# Led_PCB_v2_0.net
KiCad netlist of a schematic drawn in EAGLE
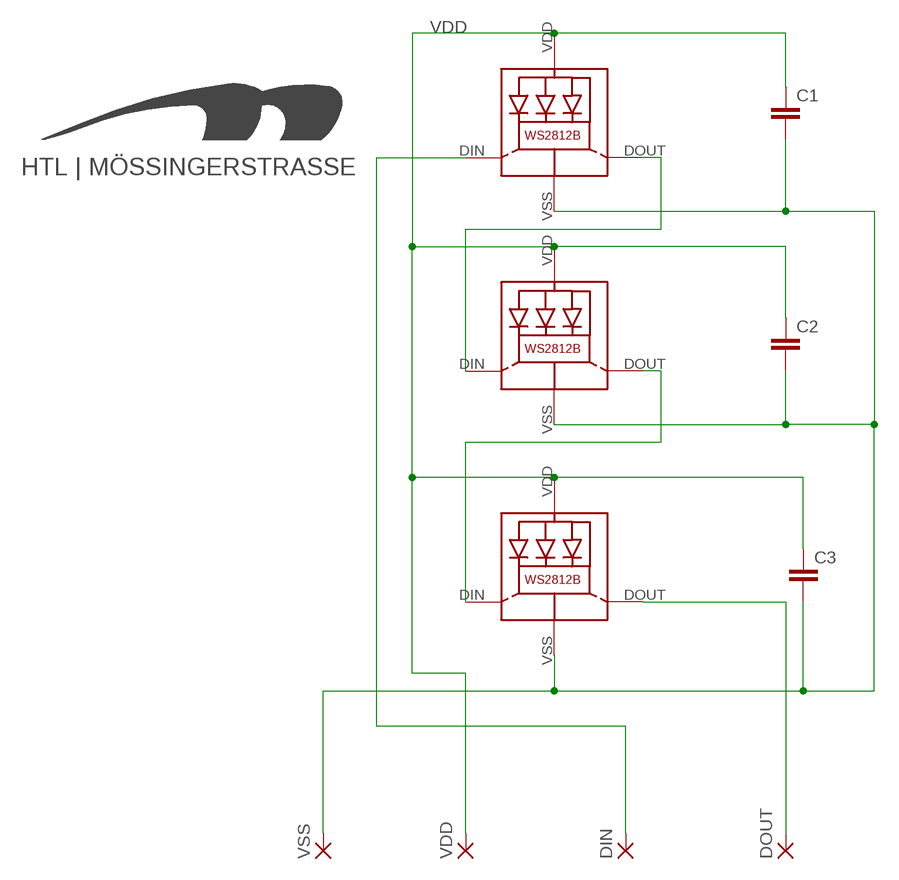
[diagram p0: schematic, sheet 1]

(export (version "E")
  (design (tool "Eeschema 10.0.6"))
  (components
    (comp (ref "C1")
      (value "C-EUC0805")
      (footprint "eagle-import:C0805")
      (libsource (lib "eagle-import") (part "C-EUC0805"))
    )
    (comp (ref "C2")
      (value "C-EUC0805")
      (footprint "eagle-import:C0805")
      (libsource (lib "eagle-import") (part "C-EUC0805"))
    )
    (comp (ref "C3")
      (value "C-EUC0805")
      (footprint "eagle-import:C0805")
      (libsource (lib "eagle-import") (part "C-EUC0805"))
    )
    (comp (ref "DIN")
      (value "SMD2")
      (footprint "eagle-import:SMD1,27-2,54")
      (libsource (lib "eagle-import") (part "SMD2"))
    )
    (comp (ref "DOUT")
      (value "SMD2")
      (footprint "eagle-import:SMD1,27-2,54")
      (libsource (lib "eagle-import") (part "SMD2"))
    )
    (comp (ref "LED1")
      (value "WS2812B")
      (footprint "eagle-import:WS2812B")
      (libsource (lib "eagle-import") (part "WS2812B"))
    )
    (comp (ref "LED2")
      (value "WS2812B")
      (footprint "eagle-import:WS2812B")
      (libsource (lib "eagle-import") (part "WS2812B"))
    )
    (comp (ref "LED3")
      (value "WS2812B")
      (footprint "eagle-import:WS2812B")
      (libsource (lib "eagle-import") (part "WS2812B"))
    )
    (comp (ref "U$1")
      (value "HTL_LOGOTOP_8MM")
      (footprint "eagle-import:LOGOTOP_8")
      (libsource (lib "eagle-import") (part "HTL_LOGOTOP_8MM"))
    )
    (comp (ref "VDD")
      (value "SMD2")
      (footprint "eagle-import:SMD1,27-2,54")
      (libsource (lib "eagle-import") (part "SMD2"))
    )
    (comp (ref "VSS")
      (value "SMD2")
      (footprint "eagle-import:SMD1,27-2,54")
      (libsource (lib "eagle-import") (part "SMD2"))
    )
  )
  (nets
    (net (code "1") (name "/VDD") (class "Default")
      (node (ref "C1") (pin "1") (pinfunction "1_1") (pintype "passive"))
      (node (ref "C2") (pin "1") (pinfunction "1_1") (pintype "passive"))
      (node (ref "C3") (pin "1") (pinfunction "1_1") (pintype "passive"))
      (node (ref "LED1") (pin "VDD") (pinfunction "VDD_VDD") (pintype "power_in"))
      (node (ref "LED2") (pin "VDD") (pinfunction "VDD_VDD") (pintype "power_in"))
      (node (ref "LED3") (pin "VDD") (pinfunction "VDD_VDD") (pintype "power_in"))
      (node (ref "VDD") (pin "1") (pinfunction "P_1") (pintype "passive"))
    )
    (net (code "2") (name "Net-(DIN-P)") (class "Default")
      (node (ref "DIN") (pin "1") (pinfunction "P_1") (pintype "passive"))
      (node (ref "LED1") (pin "DIN") (pinfunction "DI_DIN") (pintype "input"))
    )
    (net (code "3") (name "Net-(DOUT-P)") (class "Default")
      (node (ref "DOUT") (pin "1") (pinfunction "P_1") (pintype "passive"))
      (node (ref "LED3") (pin "DOUT") (pinfunction "DO_DOUT") (pintype "output"))
    )
    (net (code "4") (name "Net-(LED1-DO)") (class "Default")
      (node (ref "LED1") (pin "DOUT") (pinfunction "DO_DOUT") (pintype "output"))
      (node (ref "LED2") (pin "DIN") (pinfunction "DI_DIN") (pintype "input"))
    )
    (net (code "5") (name "Net-(LED1-GND)") (class "Default")
      (node (ref "C1") (pin "2") (pinfunction "2_2") (pintype "passive"))
      (node (ref "C2") (pin "2") (pinfunction "2_2") (pintype "passive"))
      (node (ref "C3") (pin "2") (pinfunction "2_2") (pintype "passive"))
      (node (ref "LED1") (pin "VSS") (pinfunction "GND_VSS") (pintype "power_in"))
      (node (ref "LED2") (pin "VSS") (pinfunction "GND_VSS") (pintype "power_in"))
      (node (ref "LED3") (pin "VSS") (pinfunction "GND_VSS") (pintype "power_in"))
      (node (ref "VSS") (pin "1") (pinfunction "P_1") (pintype "passive"))
    )
    (net (code "6") (name "Net-(LED2-DO)") (class "Default")
      (node (ref "LED2") (pin "DOUT") (pinfunction "DO_DOUT") (pintype "output"))
      (node (ref "LED3") (pin "DIN") (pinfunction "DI_DIN") (pintype "input"))
    )
  )
)
